# writecard.net
KiCad netlist of a schematic drawn in EAGLE
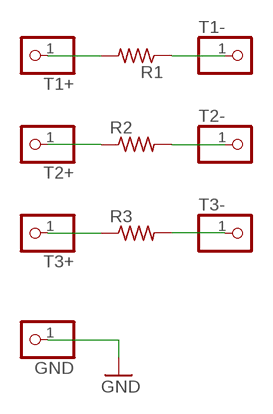
[diagram p0: schematic, sheet 1]

(export (version "E")
  (design (tool "Eeschema 10.0.6"))
  (components
    (comp (ref "GND")
      (value "PINHD-1X1")
      (footprint "eagle-import:1X01")
      (libsource (lib "eagle-import") (part "PINHD-1X1"))
    )
    (comp (ref "R1")
      (value "R-US_R2512")
      (footprint "eagle-import:R2512")
      (libsource (lib "eagle-import") (part "R-US_R2512"))
    )
    (comp (ref "R2")
      (value "R-US_R2512")
      (footprint "eagle-import:R2512")
      (libsource (lib "eagle-import") (part "R-US_R2512"))
    )
    (comp (ref "R3")
      (value "R-US_R2512")
      (footprint "eagle-import:R2512")
      (libsource (lib "eagle-import") (part "R-US_R2512"))
    )
    (comp (ref "T1+")
      (value "PINHD-1X1")
      (footprint "eagle-import:1X01")
      (libsource (lib "eagle-import") (part "PINHD-1X1"))
    )
    (comp (ref "T1-")
      (value "PINHD-1X1")
      (footprint "eagle-import:1X01")
      (libsource (lib "eagle-import") (part "PINHD-1X1"))
    )
    (comp (ref "T2+")
      (value "PINHD-1X1")
      (footprint "eagle-import:1X01")
      (libsource (lib "eagle-import") (part "PINHD-1X1"))
    )
    (comp (ref "T2-")
      (value "PINHD-1X1")
      (footprint "eagle-import:1X01")
      (libsource (lib "eagle-import") (part "PINHD-1X1"))
    )
    (comp (ref "T3+")
      (value "PINHD-1X1")
      (footprint "eagle-import:1X01")
      (libsource (lib "eagle-import") (part "PINHD-1X1"))
    )
    (comp (ref "T3-")
      (value "PINHD-1X1")
      (footprint "eagle-import:1X01")
      (libsource (lib "eagle-import") (part "PINHD-1X1"))
    )
  )
  (nets
    (net (code "1") (name "GND") (class "Default")
      (node (ref "GND") (pin "1") (pinfunction "1_1") (pintype "passive"))
    )
    (net (code "2") (name "Net-(R1-Pad1)") (class "Default")
      (node (ref "R1") (pin "1") (pinfunction "1_1") (pintype "passive"))
      (node (ref "T1-") (pin "1") (pinfunction "1_1") (pintype "passive"))
    )
    (net (code "3") (name "Net-(R1-Pad2)") (class "Default")
      (node (ref "R1") (pin "2") (pinfunction "2_2") (pintype "passive"))
      (node (ref "T1+") (pin "1") (pinfunction "1_1") (pintype "passive"))
    )
    (net (code "4") (name "Net-(R2-Pad1)") (class "Default")
      (node (ref "R2") (pin "1") (pinfunction "1_1") (pintype "passive"))
      (node (ref "T2+") (pin "1") (pinfunction "1_1") (pintype "passive"))
    )
    (net (code "5") (name "Net-(R2-Pad2)") (class "Default")
      (node (ref "R2") (pin "2") (pinfunction "2_2") (pintype "passive"))
      (node (ref "T2-") (pin "1") (pinfunction "1_1") (pintype "passive"))
    )
    (net (code "6") (name "Net-(R3-Pad1)") (class "Default")
      (node (ref "R3") (pin "1") (pinfunction "1_1") (pintype "passive"))
      (node (ref "T3+") (pin "1") (pinfunction "1_1") (pintype "passive"))
    )
    (net (code "7") (name "Net-(R3-Pad2)") (class "Default")
      (node (ref "R3") (pin "2") (pinfunction "2_2") (pintype "passive"))
      (node (ref "T3-") (pin "1") (pinfunction "1_1") (pintype "passive"))
    )
  )
)
